# LED_Cube_V5.net
KiCad netlist of a schematic drawn in EAGLE
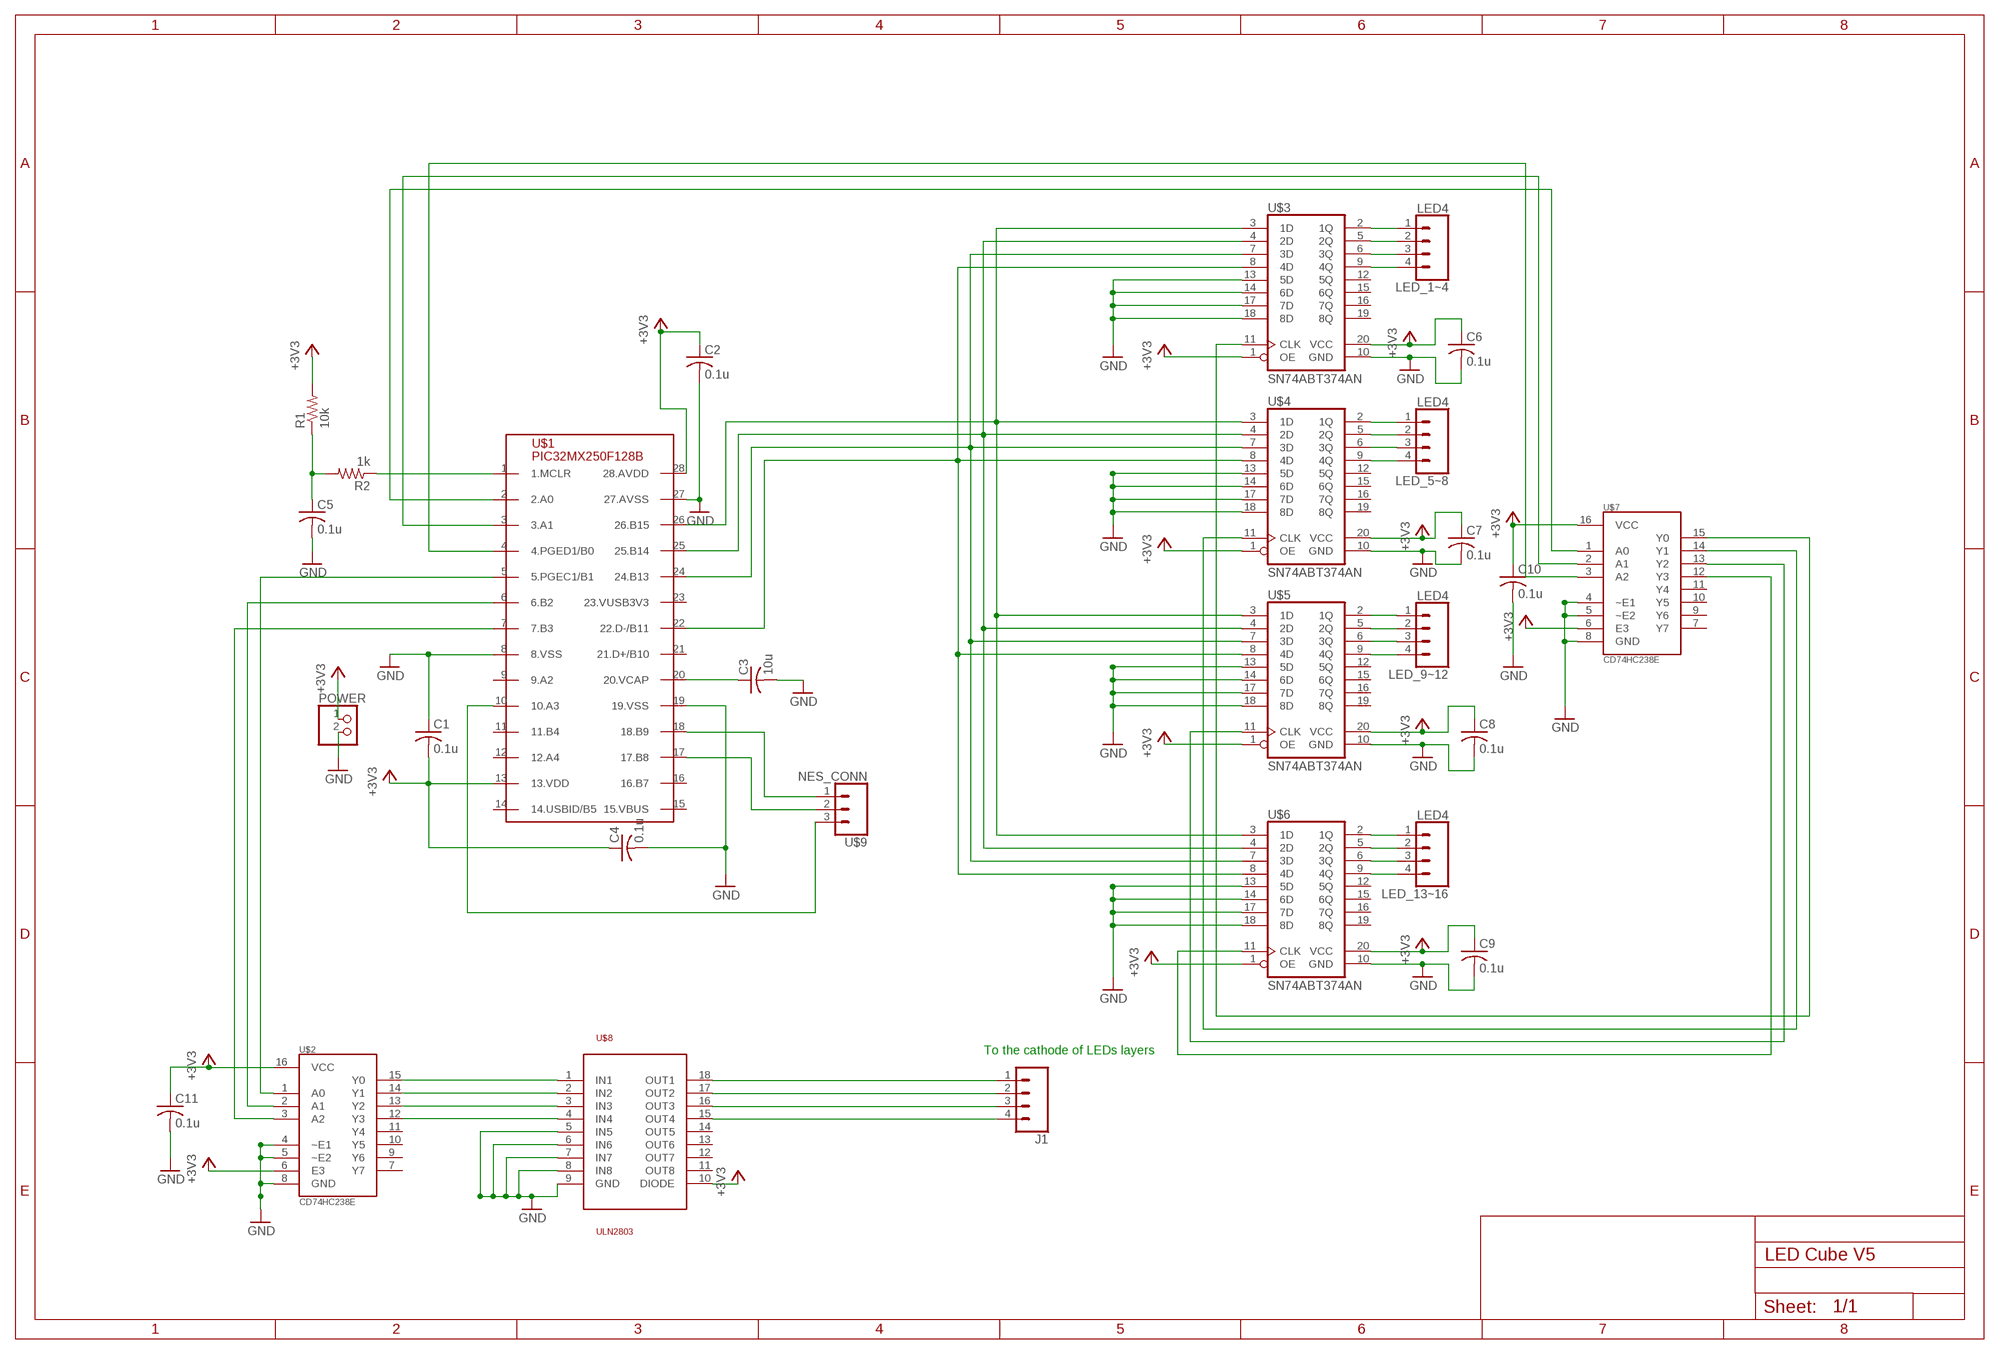
[diagram p0: schematic, sheet 1]

(export (version "E")
  (design (tool "Eeschema 10.0.6"))
  (components
    (comp (ref "C1")
      (value "0.1u")
      (footprint "eagle-import:C025-025X050")
      (libsource (lib "eagle-import") (part "C-US025-025X050"))
    )
    (comp (ref "C2")
      (value "0.1u")
      (footprint "eagle-import:C025-025X050")
      (libsource (lib "eagle-import") (part "C-US025-025X050"))
    )
    (comp (ref "C3")
      (value "10u")
      (footprint "eagle-import:C025-025X050")
      (libsource (lib "eagle-import") (part "C-US025-025X050"))
    )
    (comp (ref "C4")
      (value "0.1u")
      (footprint "eagle-import:C025-025X050")
      (libsource (lib "eagle-import") (part "C-US025-025X050"))
    )
    (comp (ref "C5")
      (value "0.1u")
      (footprint "eagle-import:C025-025X050")
      (libsource (lib "eagle-import") (part "C-US025-025X050"))
    )
    (comp (ref "C6")
      (value "0.1u")
      (footprint "eagle-import:C025-025X050")
      (libsource (lib "eagle-import") (part "C-US025-025X050"))
    )
    (comp (ref "C7")
      (value "0.1u")
      (footprint "eagle-import:C025-025X050")
      (libsource (lib "eagle-import") (part "C-US025-025X050"))
    )
    (comp (ref "C8")
      (value "0.1u")
      (footprint "eagle-import:C025-025X050")
      (libsource (lib "eagle-import") (part "C-US025-025X050"))
    )
    (comp (ref "C9")
      (value "0.1u")
      (footprint "eagle-import:C025-025X050")
      (libsource (lib "eagle-import") (part "C-US025-025X050"))
    )
    (comp (ref "C10")
      (value "0.1u")
      (footprint "eagle-import:C025-025X050")
      (libsource (lib "eagle-import") (part "C-US025-025X050"))
    )
    (comp (ref "C11")
      (value "0.1u")
      (footprint "eagle-import:C025-025X050")
      (libsource (lib "eagle-import") (part "C-US025-025X050"))
    )
    (comp (ref "J1")
      (value "CONN_04")
      (footprint "eagle-import:1X04")
      (libsource (lib "eagle-import") (part "CONN_04"))
    )
    (comp (ref "LED_1~4")
      (value "LED4")
      (footprint "eagle-import:1X04")
      (libsource (lib "eagle-import") (part "LED4"))
    )
    (comp (ref "LED_5~8")
      (value "LED4")
      (footprint "eagle-import:1X04")
      (libsource (lib "eagle-import") (part "LED4"))
    )
    (comp (ref "LED_9~12")
      (value "LED4")
      (footprint "eagle-import:1X04")
      (libsource (lib "eagle-import") (part "LED4"))
    )
    (comp (ref "LED_13~16")
      (value "LED4")
      (footprint "eagle-import:1X04")
      (libsource (lib "eagle-import") (part "LED4"))
    )
    (comp (ref "POWER")
      (value "PINHD-1X2")
      (footprint "eagle-import:1X02")
      (libsource (lib "eagle-import") (part "PINHD-1X2"))
    )
    (comp (ref "R1")
      (value "10k")
      (footprint "eagle-import:0204_7")
      (libsource (lib "eagle-import") (part "R-US_0204/7"))
    )
    (comp (ref "R2")
      (value "1k")
      (footprint "eagle-import:0204_7")
      (libsource (lib "eagle-import") (part "R-US_0204/7"))
    )
    (comp (ref "U$1")
      (value "PIC32MX250F128B")
      (footprint "eagle-import:DIL28-3")
      (libsource (lib "eagle-import") (part "PIC32MX250F128B"))
    )
    (comp (ref "U$2")
      (value "CD74HC238E")
      (footprint "eagle-import:DIL16")
      (libsource (lib "eagle-import") (part "CD74HC238E"))
    )
    (comp (ref "U$3")
      (value "SN74ABT374AN")
      (footprint "eagle-import:DIL20")
      (libsource (lib "eagle-import") (part "SN74ABT374AN"))
    )
    (comp (ref "U$4")
      (value "SN74ABT374AN")
      (footprint "eagle-import:DIL20")
      (libsource (lib "eagle-import") (part "SN74ABT374AN"))
    )
    (comp (ref "U$5")
      (value "SN74ABT374AN")
      (footprint "eagle-import:DIL20")
      (libsource (lib "eagle-import") (part "SN74ABT374AN"))
    )
    (comp (ref "U$6")
      (value "SN74ABT374AN")
      (footprint "eagle-import:DIL20")
      (libsource (lib "eagle-import") (part "SN74ABT374AN"))
    )
    (comp (ref "U$7")
      (value "CD74HC238E")
      (footprint "eagle-import:DIL16")
      (libsource (lib "eagle-import") (part "CD74HC238E"))
    )
    (comp (ref "U$8")
      (value "ULN2803")
      (footprint "eagle-import:SO18L")
      (libsource (lib "eagle-import") (part "ULN2803"))
    )
    (comp (ref "U$9")
      (value "NES_CONN")
      (footprint "eagle-import:1X03")
      (libsource (lib "eagle-import") (part "NES_CONN"))
    )
  )
  (nets
    (net (code "1") (name "+3V3") (class "Default")
      (node (ref "C1") (pin "2") (pinfunction "2_2") (pintype "passive"))
      (node (ref "C10") (pin "1") (pinfunction "1_1") (pintype "passive"))
      (node (ref "C11") (pin "1") (pinfunction "1_1") (pintype "passive"))
      (node (ref "C2") (pin "1") (pinfunction "1_1") (pintype "passive"))
      (node (ref "C4") (pin "1") (pinfunction "1_1") (pintype "passive"))
      (node (ref "C6") (pin "1") (pinfunction "1_1") (pintype "passive"))
      (node (ref "C7") (pin "1") (pinfunction "1_1") (pintype "passive"))
      (node (ref "C8") (pin "1") (pinfunction "1_1") (pintype "passive"))
      (node (ref "C9") (pin "1") (pinfunction "1_1") (pintype "passive"))
      (node (ref "POWER") (pin "1") (pinfunction "1_1") (pintype "passive"))
      (node (ref "R1") (pin "2") (pinfunction "2_2") (pintype "passive"))
      (node (ref "U$1") (pin "13") (pinfunction "13.VDD_13") (pintype "bidirectional"))
      (node (ref "U$1") (pin "28") (pinfunction "28.AVDD_28") (pintype "bidirectional"))
      (node (ref "U$2") (pin "16") (pinfunction "VCC_16") (pintype "bidirectional"))
      (node (ref "U$2") (pin "6") (pinfunction "E3_6") (pintype "bidirectional"))
      (node (ref "U$3") (pin "1") (pinfunction "OE_1") (pintype "input"))
      (node (ref "U$3") (pin "20") (pinfunction "VCC_20") (pintype "bidirectional"))
      (node (ref "U$4") (pin "1") (pinfunction "OE_1") (pintype "input"))
      (node (ref "U$4") (pin "20") (pinfunction "VCC_20") (pintype "bidirectional"))
      (node (ref "U$5") (pin "1") (pinfunction "OE_1") (pintype "input"))
      (node (ref "U$5") (pin "20") (pinfunction "VCC_20") (pintype "bidirectional"))
      (node (ref "U$6") (pin "1") (pinfunction "OE_1") (pintype "input"))
      (node (ref "U$6") (pin "20") (pinfunction "VCC_20") (pintype "bidirectional"))
      (node (ref "U$7") (pin "16") (pinfunction "VCC_16") (pintype "bidirectional"))
      (node (ref "U$7") (pin "6") (pinfunction "E3_6") (pintype "bidirectional"))
      (node (ref "U$8") (pin "10") (pinfunction "DIODE_10") (pintype "power_in"))
    )
    (net (code "2") (name "GND") (class "Default")
      (node (ref "C1") (pin "1") (pinfunction "1_1") (pintype "passive"))
      (node (ref "C10") (pin "2") (pinfunction "2_2") (pintype "passive"))
      (node (ref "C11") (pin "2") (pinfunction "2_2") (pintype "passive"))
      (node (ref "C2") (pin "2") (pinfunction "2_2") (pintype "passive"))
      (node (ref "C3") (pin "2") (pinfunction "2_2") (pintype "passive"))
      (node (ref "C4") (pin "2") (pinfunction "2_2") (pintype "passive"))
      (node (ref "C5") (pin "2") (pinfunction "2_2") (pintype "passive"))
      (node (ref "C6") (pin "2") (pinfunction "2_2") (pintype "passive"))
      (node (ref "C7") (pin "2") (pinfunction "2_2") (pintype "passive"))
      (node (ref "C8") (pin "2") (pinfunction "2_2") (pintype "passive"))
      (node (ref "C9") (pin "2") (pinfunction "2_2") (pintype "passive"))
      (node (ref "POWER") (pin "2") (pinfunction "2_2") (pintype "passive"))
      (node (ref "U$1") (pin "19") (pinfunction "19.VSS_19") (pintype "bidirectional"))
      (node (ref "U$1") (pin "27") (pinfunction "27.AVSS_27") (pintype "bidirectional"))
      (node (ref "U$1") (pin "8") (pinfunction "8.VSS_8") (pintype "bidirectional"))
      (node (ref "U$2") (pin "4") (pinfunction "~{E1}_4") (pintype "bidirectional"))
      (node (ref "U$2") (pin "5") (pinfunction "~{E2}_5") (pintype "bidirectional"))
      (node (ref "U$2") (pin "8") (pinfunction "GND_8") (pintype "bidirectional"))
      (node (ref "U$3") (pin "10") (pinfunction "GND_10") (pintype "bidirectional"))
      (node (ref "U$3") (pin "13") (pinfunction "5D_13") (pintype "input"))
      (node (ref "U$3") (pin "14") (pinfunction "6D_14") (pintype "input"))
      (node (ref "U$3") (pin "17") (pinfunction "7D_17") (pintype "input"))
      (node (ref "U$3") (pin "18") (pinfunction "8D_18") (pintype "input"))
      (node (ref "U$4") (pin "10") (pinfunction "GND_10") (pintype "bidirectional"))
      (node (ref "U$4") (pin "13") (pinfunction "5D_13") (pintype "input"))
      (node (ref "U$4") (pin "14") (pinfunction "6D_14") (pintype "input"))
      (node (ref "U$4") (pin "17") (pinfunction "7D_17") (pintype "input"))
      (node (ref "U$4") (pin "18") (pinfunction "8D_18") (pintype "input"))
      (node (ref "U$5") (pin "10") (pinfunction "GND_10") (pintype "bidirectional"))
      (node (ref "U$5") (pin "13") (pinfunction "5D_13") (pintype "input"))
      (node (ref "U$5") (pin "14") (pinfunction "6D_14") (pintype "input"))
      (node (ref "U$5") (pin "17") (pinfunction "7D_17") (pintype "input"))
      (node (ref "U$5") (pin "18") (pinfunction "8D_18") (pintype "input"))
      (node (ref "U$6") (pin "10") (pinfunction "GND_10") (pintype "bidirectional"))
      (node (ref "U$6") (pin "13") (pinfunction "5D_13") (pintype "input"))
      (node (ref "U$6") (pin "14") (pinfunction "6D_14") (pintype "input"))
      (node (ref "U$6") (pin "17") (pinfunction "7D_17") (pintype "input"))
      (node (ref "U$6") (pin "18") (pinfunction "8D_18") (pintype "input"))
      (node (ref "U$7") (pin "4") (pinfunction "~{E1}_4") (pintype "bidirectional"))
      (node (ref "U$7") (pin "5") (pinfunction "~{E2}_5") (pintype "bidirectional"))
      (node (ref "U$7") (pin "8") (pinfunction "GND_8") (pintype "bidirectional"))
      (node (ref "U$8") (pin "5") (pinfunction "IN5_5") (pintype "input"))
      (node (ref "U$8") (pin "6") (pinfunction "IN6_6") (pintype "input"))
      (node (ref "U$8") (pin "7") (pinfunction "IN7_7") (pintype "input"))
      (node (ref "U$8") (pin "8") (pinfunction "IN8_8") (pintype "input"))
      (node (ref "U$8") (pin "9") (pinfunction "GND_9") (pintype "power_in"))
    )
    (net (code "3") (name "Net-(C5-Pad1)") (class "Default")
      (node (ref "C5") (pin "1") (pinfunction "1_1") (pintype "passive"))
      (node (ref "R1") (pin "1") (pinfunction "1_1") (pintype "passive"))
      (node (ref "R2") (pin "2") (pinfunction "2_2") (pintype "passive"))
    )
    (net (code "4") (name "Net-(U$1-1.MCLR)") (class "Default")
      (node (ref "R2") (pin "1") (pinfunction "1_1") (pintype "passive"))
      (node (ref "U$1") (pin "1") (pinfunction "1.MCLR_1") (pintype "bidirectional"))
    )
    (net (code "5") (name "Net-(U$1-2.A0)") (class "Default")
      (node (ref "U$1") (pin "2") (pinfunction "2.A0_2") (pintype "bidirectional"))
      (node (ref "U$7") (pin "1") (pinfunction "A0_1") (pintype "bidirectional"))
    )
    (net (code "6") (name "Net-(U$1-3.A1)") (class "Default")
      (node (ref "U$1") (pin "3") (pinfunction "3.A1_3") (pintype "bidirectional"))
      (node (ref "U$7") (pin "2") (pinfunction "A1_2") (pintype "bidirectional"))
    )
    (net (code "7") (name "Net-(U$1-4.PGED1{slash}B0)") (class "Default")
      (node (ref "U$1") (pin "4") (pinfunction "4.PGED1/B0_4") (pintype "bidirectional"))
      (node (ref "U$7") (pin "3") (pinfunction "A2_3") (pintype "bidirectional"))
    )
    (net (code "8") (name "Net-(U$1-5.PGEC1{slash}B1)") (class "Default")
      (node (ref "U$1") (pin "5") (pinfunction "5.PGEC1/B1_5") (pintype "bidirectional"))
      (node (ref "U$2") (pin "1") (pinfunction "A0_1") (pintype "bidirectional"))
    )
    (net (code "9") (name "Net-(U$1-6.B2)") (class "Default")
      (node (ref "U$1") (pin "6") (pinfunction "6.B2_6") (pintype "bidirectional"))
      (node (ref "U$2") (pin "2") (pinfunction "A1_2") (pintype "bidirectional"))
    )
    (net (code "10") (name "Net-(U$1-7.B3)") (class "Default")
      (node (ref "U$1") (pin "7") (pinfunction "7.B3_7") (pintype "bidirectional"))
      (node (ref "U$2") (pin "3") (pinfunction "A2_3") (pintype "bidirectional"))
    )
    (net (code "11") (name "Net-(U$1-10.A3)") (class "Default")
      (node (ref "U$1") (pin "10") (pinfunction "10.A3_10") (pintype "bidirectional"))
      (node (ref "U$9") (pin "3") (pinfunction "3_3") (pintype "passive"))
    )
    (net (code "12") (name "Net-(U$1-17.B8)") (class "Default")
      (node (ref "U$1") (pin "17") (pinfunction "17.B8_17") (pintype "bidirectional"))
      (node (ref "U$9") (pin "2") (pinfunction "2_2") (pintype "passive"))
    )
    (net (code "13") (name "Net-(U$1-18.B9)") (class "Default")
      (node (ref "U$1") (pin "18") (pinfunction "18.B9_18") (pintype "bidirectional"))
      (node (ref "U$9") (pin "1") (pinfunction "1_1") (pintype "passive"))
    )
    (net (code "14") (name "Net-(U$1-20.VCAP)") (class "Default")
      (node (ref "C3") (pin "1") (pinfunction "1_1") (pintype "passive"))
      (node (ref "U$1") (pin "20") (pinfunction "20.VCAP_20") (pintype "bidirectional"))
    )
    (net (code "15") (name "Net-(U$1-22.D-{slash}B11)") (class "Default")
      (node (ref "U$1") (pin "22") (pinfunction "22.D-/B11_22") (pintype "bidirectional"))
      (node (ref "U$3") (pin "8") (pinfunction "4D_8") (pintype "input"))
      (node (ref "U$4") (pin "8") (pinfunction "4D_8") (pintype "input"))
      (node (ref "U$5") (pin "8") (pinfunction "4D_8") (pintype "input"))
      (node (ref "U$6") (pin "8") (pinfunction "4D_8") (pintype "input"))
    )
    (net (code "16") (name "Net-(U$1-24.B13)") (class "Default")
      (node (ref "U$1") (pin "24") (pinfunction "24.B13_24") (pintype "bidirectional"))
      (node (ref "U$3") (pin "7") (pinfunction "3D_7") (pintype "input"))
      (node (ref "U$4") (pin "7") (pinfunction "3D_7") (pintype "input"))
      (node (ref "U$5") (pin "7") (pinfunction "3D_7") (pintype "input"))
      (node (ref "U$6") (pin "7") (pinfunction "3D_7") (pintype "input"))
    )
    (net (code "17") (name "Net-(U$1-25.B14)") (class "Default")
      (node (ref "U$1") (pin "25") (pinfunction "25.B14_25") (pintype "bidirectional"))
      (node (ref "U$3") (pin "4") (pinfunction "2D_4") (pintype "input"))
      (node (ref "U$4") (pin "4") (pinfunction "2D_4") (pintype "input"))
      (node (ref "U$5") (pin "4") (pinfunction "2D_4") (pintype "input"))
      (node (ref "U$6") (pin "4") (pinfunction "2D_4") (pintype "input"))
    )
    (net (code "18") (name "Net-(U$1-26.B15)") (class "Default")
      (node (ref "U$1") (pin "26") (pinfunction "26.B15_26") (pintype "bidirectional"))
      (node (ref "U$3") (pin "3") (pinfunction "1D_3") (pintype "input"))
      (node (ref "U$4") (pin "3") (pinfunction "1D_3") (pintype "input"))
      (node (ref "U$5") (pin "3") (pinfunction "1D_3") (pintype "input"))
      (node (ref "U$6") (pin "3") (pinfunction "1D_3") (pintype "input"))
    )
    (net (code "19") (name "Net-(U$2-Y0)") (class "Default")
      (node (ref "U$2") (pin "15") (pinfunction "Y0_15") (pintype "bidirectional"))
      (node (ref "U$8") (pin "1") (pinfunction "IN1_1") (pintype "input"))
    )
    (net (code "20") (name "Net-(U$2-Y1)") (class "Default")
      (node (ref "U$2") (pin "14") (pinfunction "Y1_14") (pintype "bidirectional"))
      (node (ref "U$8") (pin "2") (pinfunction "IN2_2") (pintype "input"))
    )
    (net (code "21") (name "Net-(U$2-Y2)") (class "Default")
      (node (ref "U$2") (pin "13") (pinfunction "Y2_13") (pintype "bidirectional"))
      (node (ref "U$8") (pin "3") (pinfunction "IN3_3") (pintype "input"))
    )
    (net (code "22") (name "Net-(U$2-Y3)") (class "Default")
      (node (ref "U$2") (pin "12") (pinfunction "Y3_12") (pintype "bidirectional"))
      (node (ref "U$8") (pin "4") (pinfunction "IN4_4") (pintype "input"))
    )
    (net (code "23") (name "Net-(U$3-1Q)") (class "Default")
      (node (ref "LED_1~4") (pin "1") (pinfunction "1_1") (pintype "passive"))
      (node (ref "U$3") (pin "2") (pinfunction "1Q_2") (pintype "tri_state"))
    )
    (net (code "24") (name "Net-(U$3-2Q)") (class "Default")
      (node (ref "LED_1~4") (pin "2") (pinfunction "2_2") (pintype "passive"))
      (node (ref "U$3") (pin "5") (pinfunction "2Q_5") (pintype "tri_state"))
    )
    (net (code "25") (name "Net-(U$3-3Q)") (class "Default")
      (node (ref "LED_1~4") (pin "3") (pinfunction "3_3") (pintype "passive"))
      (node (ref "U$3") (pin "6") (pinfunction "3Q_6") (pintype "tri_state"))
    )
    (net (code "26") (name "Net-(U$3-4Q)") (class "Default")
      (node (ref "LED_1~4") (pin "4") (pinfunction "4_4") (pintype "passive"))
      (node (ref "U$3") (pin "9") (pinfunction "4Q_9") (pintype "tri_state"))
    )
    (net (code "27") (name "Net-(U$3-CLK)") (class "Default")
      (node (ref "U$3") (pin "11") (pinfunction "CLK_11") (pintype "input"))
      (node (ref "U$7") (pin "15") (pinfunction "Y0_15") (pintype "bidirectional"))
    )
    (net (code "28") (name "Net-(U$4-1Q)") (class "Default")
      (node (ref "LED_5~8") (pin "1") (pinfunction "1_1") (pintype "passive"))
      (node (ref "U$4") (pin "2") (pinfunction "1Q_2") (pintype "tri_state"))
    )
    (net (code "29") (name "Net-(U$4-2Q)") (class "Default")
      (node (ref "LED_5~8") (pin "2") (pinfunction "2_2") (pintype "passive"))
      (node (ref "U$4") (pin "5") (pinfunction "2Q_5") (pintype "tri_state"))
    )
    (net (code "30") (name "Net-(U$4-3Q)") (class "Default")
      (node (ref "LED_5~8") (pin "3") (pinfunction "3_3") (pintype "passive"))
      (node (ref "U$4") (pin "6") (pinfunction "3Q_6") (pintype "tri_state"))
    )
    (net (code "31") (name "Net-(U$4-4Q)") (class "Default")
      (node (ref "LED_5~8") (pin "4") (pinfunction "4_4") (pintype "passive"))
      (node (ref "U$4") (pin "9") (pinfunction "4Q_9") (pintype "tri_state"))
    )
    (net (code "32") (name "Net-(U$4-CLK)") (class "Default")
      (node (ref "U$4") (pin "11") (pinfunction "CLK_11") (pintype "input"))
      (node (ref "U$7") (pin "14") (pinfunction "Y1_14") (pintype "bidirectional"))
    )
    (net (code "33") (name "Net-(U$5-1Q)") (class "Default")
      (node (ref "LED_9~12") (pin "1") (pinfunction "1_1") (pintype "passive"))
      (node (ref "U$5") (pin "2") (pinfunction "1Q_2") (pintype "tri_state"))
    )
    (net (code "34") (name "Net-(U$5-2Q)") (class "Default")
      (node (ref "LED_9~12") (pin "2") (pinfunction "2_2") (pintype "passive"))
      (node (ref "U$5") (pin "5") (pinfunction "2Q_5") (pintype "tri_state"))
    )
    (net (code "35") (name "Net-(U$5-3Q)") (class "Default")
      (node (ref "LED_9~12") (pin "3") (pinfunction "3_3") (pintype "passive"))
      (node (ref "U$5") (pin "6") (pinfunction "3Q_6") (pintype "tri_state"))
    )
    (net (code "36") (name "Net-(U$5-4Q)") (class "Default")
      (node (ref "LED_9~12") (pin "4") (pinfunction "4_4") (pintype "passive"))
      (node (ref "U$5") (pin "9") (pinfunction "4Q_9") (pintype "tri_state"))
    )
    (net (code "37") (name "Net-(U$5-CLK)") (class "Default")
      (node (ref "U$5") (pin "11") (pinfunction "CLK_11") (pintype "input"))
      (node (ref "U$7") (pin "13") (pinfunction "Y2_13") (pintype "bidirectional"))
    )
    (net (code "38") (name "Net-(U$6-1Q)") (class "Default")
      (node (ref "LED_13~16") (pin "1") (pinfunction "1_1") (pintype "passive"))
      (node (ref "U$6") (pin "2") (pinfunction "1Q_2") (pintype "tri_state"))
    )
    (net (code "39") (name "Net-(U$6-2Q)") (class "Default")
      (node (ref "LED_13~16") (pin "2") (pinfunction "2_2") (pintype "passive"))
      (node (ref "U$6") (pin "5") (pinfunction "2Q_5") (pintype "tri_state"))
    )
    (net (code "40") (name "Net-(U$6-3Q)") (class "Default")
      (node (ref "LED_13~16") (pin "3") (pinfunction "3_3") (pintype "passive"))
      (node (ref "U$6") (pin "6") (pinfunction "3Q_6") (pintype "tri_state"))
    )
    (net (code "41") (name "Net-(U$6-4Q)") (class "Default")
      (node (ref "LED_13~16") (pin "4") (pinfunction "4_4") (pintype "passive"))
      (node (ref "U$6") (pin "9") (pinfunction "4Q_9") (pintype "tri_state"))
    )
    (net (code "42") (name "Net-(U$6-CLK)") (class "Default")
      (node (ref "U$6") (pin "11") (pinfunction "CLK_11") (pintype "input"))
      (node (ref "U$7") (pin "12") (pinfunction "Y3_12") (pintype "bidirectional"))
    )
    (net (code "43") (name "Net-(U$8-OUT1)") (class "Default")
      (node (ref "J1") (pin "1") (pinfunction "1_1") (pintype "passive"))
      (node (ref "U$8") (pin "18") (pinfunction "OUT1_18") (pintype "open_collector"))
    )
    (net (code "44") (name "Net-(U$8-OUT2)") (class "Default")
      (node (ref "J1") (pin "2") (pinfunction "2_2") (pintype "passive"))
      (node (ref "U$8") (pin "17") (pinfunction "OUT2_17") (pintype "open_collector"))
    )
    (net (code "45") (name "Net-(U$8-OUT3)") (class "Default")
      (node (ref "J1") (pin "3") (pinfunction "3_3") (pintype "passive"))
      (node (ref "U$8") (pin "16") (pinfunction "OUT3_16") (pintype "open_collector"))
    )
    (net (code "46") (name "Net-(U$8-OUT4)") (class "Default")
      (node (ref "J1") (pin "4") (pinfunction "4_4") (pintype "passive"))
      (node (ref "U$8") (pin "15") (pinfunction "OUT4_15") (pintype "open_collector"))
    )
    (net (code "47") (name "unconnected-(U$1-9.A2-Pad9)") (class "Default")
      (node (ref "U$1") (pin "9") (pinfunction "9.A2_9") (pintype "bidirectional"))
    )
    (net (code "48") (name "unconnected-(U$1-11.B4-Pad11)") (class "Default")
      (node (ref "U$1") (pin "11") (pinfunction "11.B4_11") (pintype "bidirectional"))
    )
    (net (code "49") (name "unconnected-(U$1-12.A4-Pad12)") (class "Default")
      (node (ref "U$1") (pin "12") (pinfunction "12.A4_12") (pintype "bidirectional"))
    )
    (net (code "50") (name "unconnected-(U$1-14.USBID{slash}B5-Pad14)") (class "Default")
      (node (ref "U$1") (pin "14") (pinfunction "14.USBID/B5_14") (pintype "bidirectional"))
    )
    (net (code "51") (name "unconnected-(U$1-15.VBUS-Pad15)") (class "Default")
      (node (ref "U$1") (pin "15") (pinfunction "15.VBUS_15") (pintype "bidirectional"))
    )
    (net (code "52") (name "unconnected-(U$1-16.B7-Pad16)") (class "Default")
      (node (ref "U$1") (pin "16") (pinfunction "16.B7_16") (pintype "bidirectional"))
    )
    (net (code "53") (name "unconnected-(U$1-21.D+{slash}B10-Pad21)") (class "Default")
      (node (ref "U$1") (pin "21") (pinfunction "21.D+/B10_21") (pintype "bidirectional"))
    )
    (net (code "54") (name "unconnected-(U$1-23.VUSB3V3-Pad23)") (class "Default")
      (node (ref "U$1") (pin "23") (pinfunction "23.VUSB3V3_23") (pintype "bidirectional"))
    )
    (net (code "55") (name "unconnected-(U$2-Y4-Pad11)") (class "Default")
      (node (ref "U$2") (pin "11") (pinfunction "Y4_11") (pintype "bidirectional"))
    )
    (net (code "56") (name "unconnected-(U$2-Y5-Pad10)") (class "Default")
      (node (ref "U$2") (pin "10") (pinfunction "Y5_10") (pintype "bidirectional"))
    )
    (net (code "57") (name "unconnected-(U$2-Y6-Pad9)") (class "Default")
      (node (ref "U$2") (pin "9") (pinfunction "Y6_9") (pintype "bidirectional"))
    )
    (net (code "58") (name "unconnected-(U$2-Y7-Pad7)") (class "Default")
      (node (ref "U$2") (pin "7") (pinfunction "Y7_7") (pintype "bidirectional"))
    )
    (net (code "59") (name "unconnected-(U$3-5Q-Pad12)") (class "Default")
      (node (ref "U$3") (pin "12") (pinfunction "5Q_12") (pintype "tri_state"))
    )
    (net (code "60") (name "unconnected-(U$3-6Q-Pad15)") (class "Default")
      (node (ref "U$3") (pin "15") (pinfunction "6Q_15") (pintype "tri_state"))
    )
    (net (code "61") (name "unconnected-(U$3-7Q-Pad16)") (class "Default")
      (node (ref "U$3") (pin "16") (pinfunction "7Q_16") (pintype "tri_state"))
    )
    (net (code "62") (name "unconnected-(U$3-8Q-Pad19)") (class "Default")
      (node (ref "U$3") (pin "19") (pinfunction "8Q_19") (pintype "tri_state"))
    )
    (net (code "63") (name "unconnected-(U$4-5Q-Pad12)") (class "Default")
      (node (ref "U$4") (pin "12") (pinfunction "5Q_12") (pintype "tri_state"))
    )
    (net (code "64") (name "unconnected-(U$4-6Q-Pad15)") (class "Default")
      (node (ref "U$4") (pin "15") (pinfunction "6Q_15") (pintype "tri_state"))
    )
    (net (code "65") (name "unconnected-(U$4-7Q-Pad16)") (class "Default")
      (node (ref "U$4") (pin "16") (pinfunction "7Q_16") (pintype "tri_state"))
    )
    (net (code "66") (name "unconnected-(U$4-8Q-Pad19)") (class "Default")
      (node (ref "U$4") (pin "19") (pinfunction "8Q_19") (pintype "tri_state"))
    )
    (net (code "67") (name "unconnected-(U$5-5Q-Pad12)") (class "Default")
      (node (ref "U$5") (pin "12") (pinfunction "5Q_12") (pintype "tri_state"))
    )
    (net (code "68") (name "unconnected-(U$5-6Q-Pad15)") (class "Default")
      (node (ref "U$5") (pin "15") (pinfunction "6Q_15") (pintype "tri_state"))
    )
    (net (code "69") (name "unconnected-(U$5-7Q-Pad16)") (class "Default")
      (node (ref "U$5") (pin "16") (pinfunction "7Q_16") (pintype "tri_state"))
    )
    (net (code "70") (name "unconnected-(U$5-8Q-Pad19)") (class "Default")
      (node (ref "U$5") (pin "19") (pinfunction "8Q_19") (pintype "tri_state"))
    )
    (net (code "71") (name "unconnected-(U$6-5Q-Pad12)") (class "Default")
      (node (ref "U$6") (pin "12") (pinfunction "5Q_12") (pintype "tri_state"))
    )
    (net (code "72") (name "unconnected-(U$6-6Q-Pad15)") (class "Default")
      (node (ref "U$6") (pin "15") (pinfunction "6Q_15") (pintype "tri_state"))
    )
    (net (code "73") (name "unconnected-(U$6-7Q-Pad16)") (class "Default")
      (node (ref "U$6") (pin "16") (pinfunction "7Q_16") (pintype "tri_state"))
    )
    (net (code "74") (name "unconnected-(U$6-8Q-Pad19)") (class "Default")
      (node (ref "U$6") (pin "19") (pinfunction "8Q_19") (pintype "tri_state"))
    )
    (net (code "75") (name "unconnected-(U$7-Y4-Pad11)") (class "Default")
      (node (ref "U$7") (pin "11") (pinfunction "Y4_11") (pintype "bidirectional"))
    )
    (net (code "76") (name "unconnected-(U$7-Y5-Pad10)") (class "Default")
      (node (ref "U$7") (pin "10") (pinfunction "Y5_10") (pintype "bidirectional"))
    )
    (net (code "77") (name "unconnected-(U$7-Y6-Pad9)") (class "Default")
      (node (ref "U$7") (pin "9") (pinfunction "Y6_9") (pintype "bidirectional"))
    )
    (net (code "78") (name "unconnected-(U$7-Y7-Pad7)") (class "Default")
      (node (ref "U$7") (pin "7") (pinfunction "Y7_7") (pintype "bidirectional"))
    )
    (net (code "79") (name "unconnected-(U$8-OUT5-Pad14)") (class "Default")
      (node (ref "U$8") (pin "14") (pinfunction "OUT5_14") (pintype "open_collector"))
    )
    (net (code "80") (name "unconnected-(U$8-OUT6-Pad13)") (class "Default")
      (node (ref "U$8") (pin "13") (pinfunction "OUT6_13") (pintype "open_collector"))
    )
    (net (code "81") (name "unconnected-(U$8-OUT7-Pad12)") (class "Default")
      (node (ref "U$8") (pin "12") (pinfunction "OUT7_12") (pintype "open_collector"))
    )
    (net (code "82") (name "unconnected-(U$8-OUT8-Pad11)") (class "Default")
      (node (ref "U$8") (pin "11") (pinfunction "OUT8_11") (pintype "open_collector"))
    )
  )
)
